# Sensor_Box_LoRa.net
KiCad netlist of a schematic drawn in Altium Designer
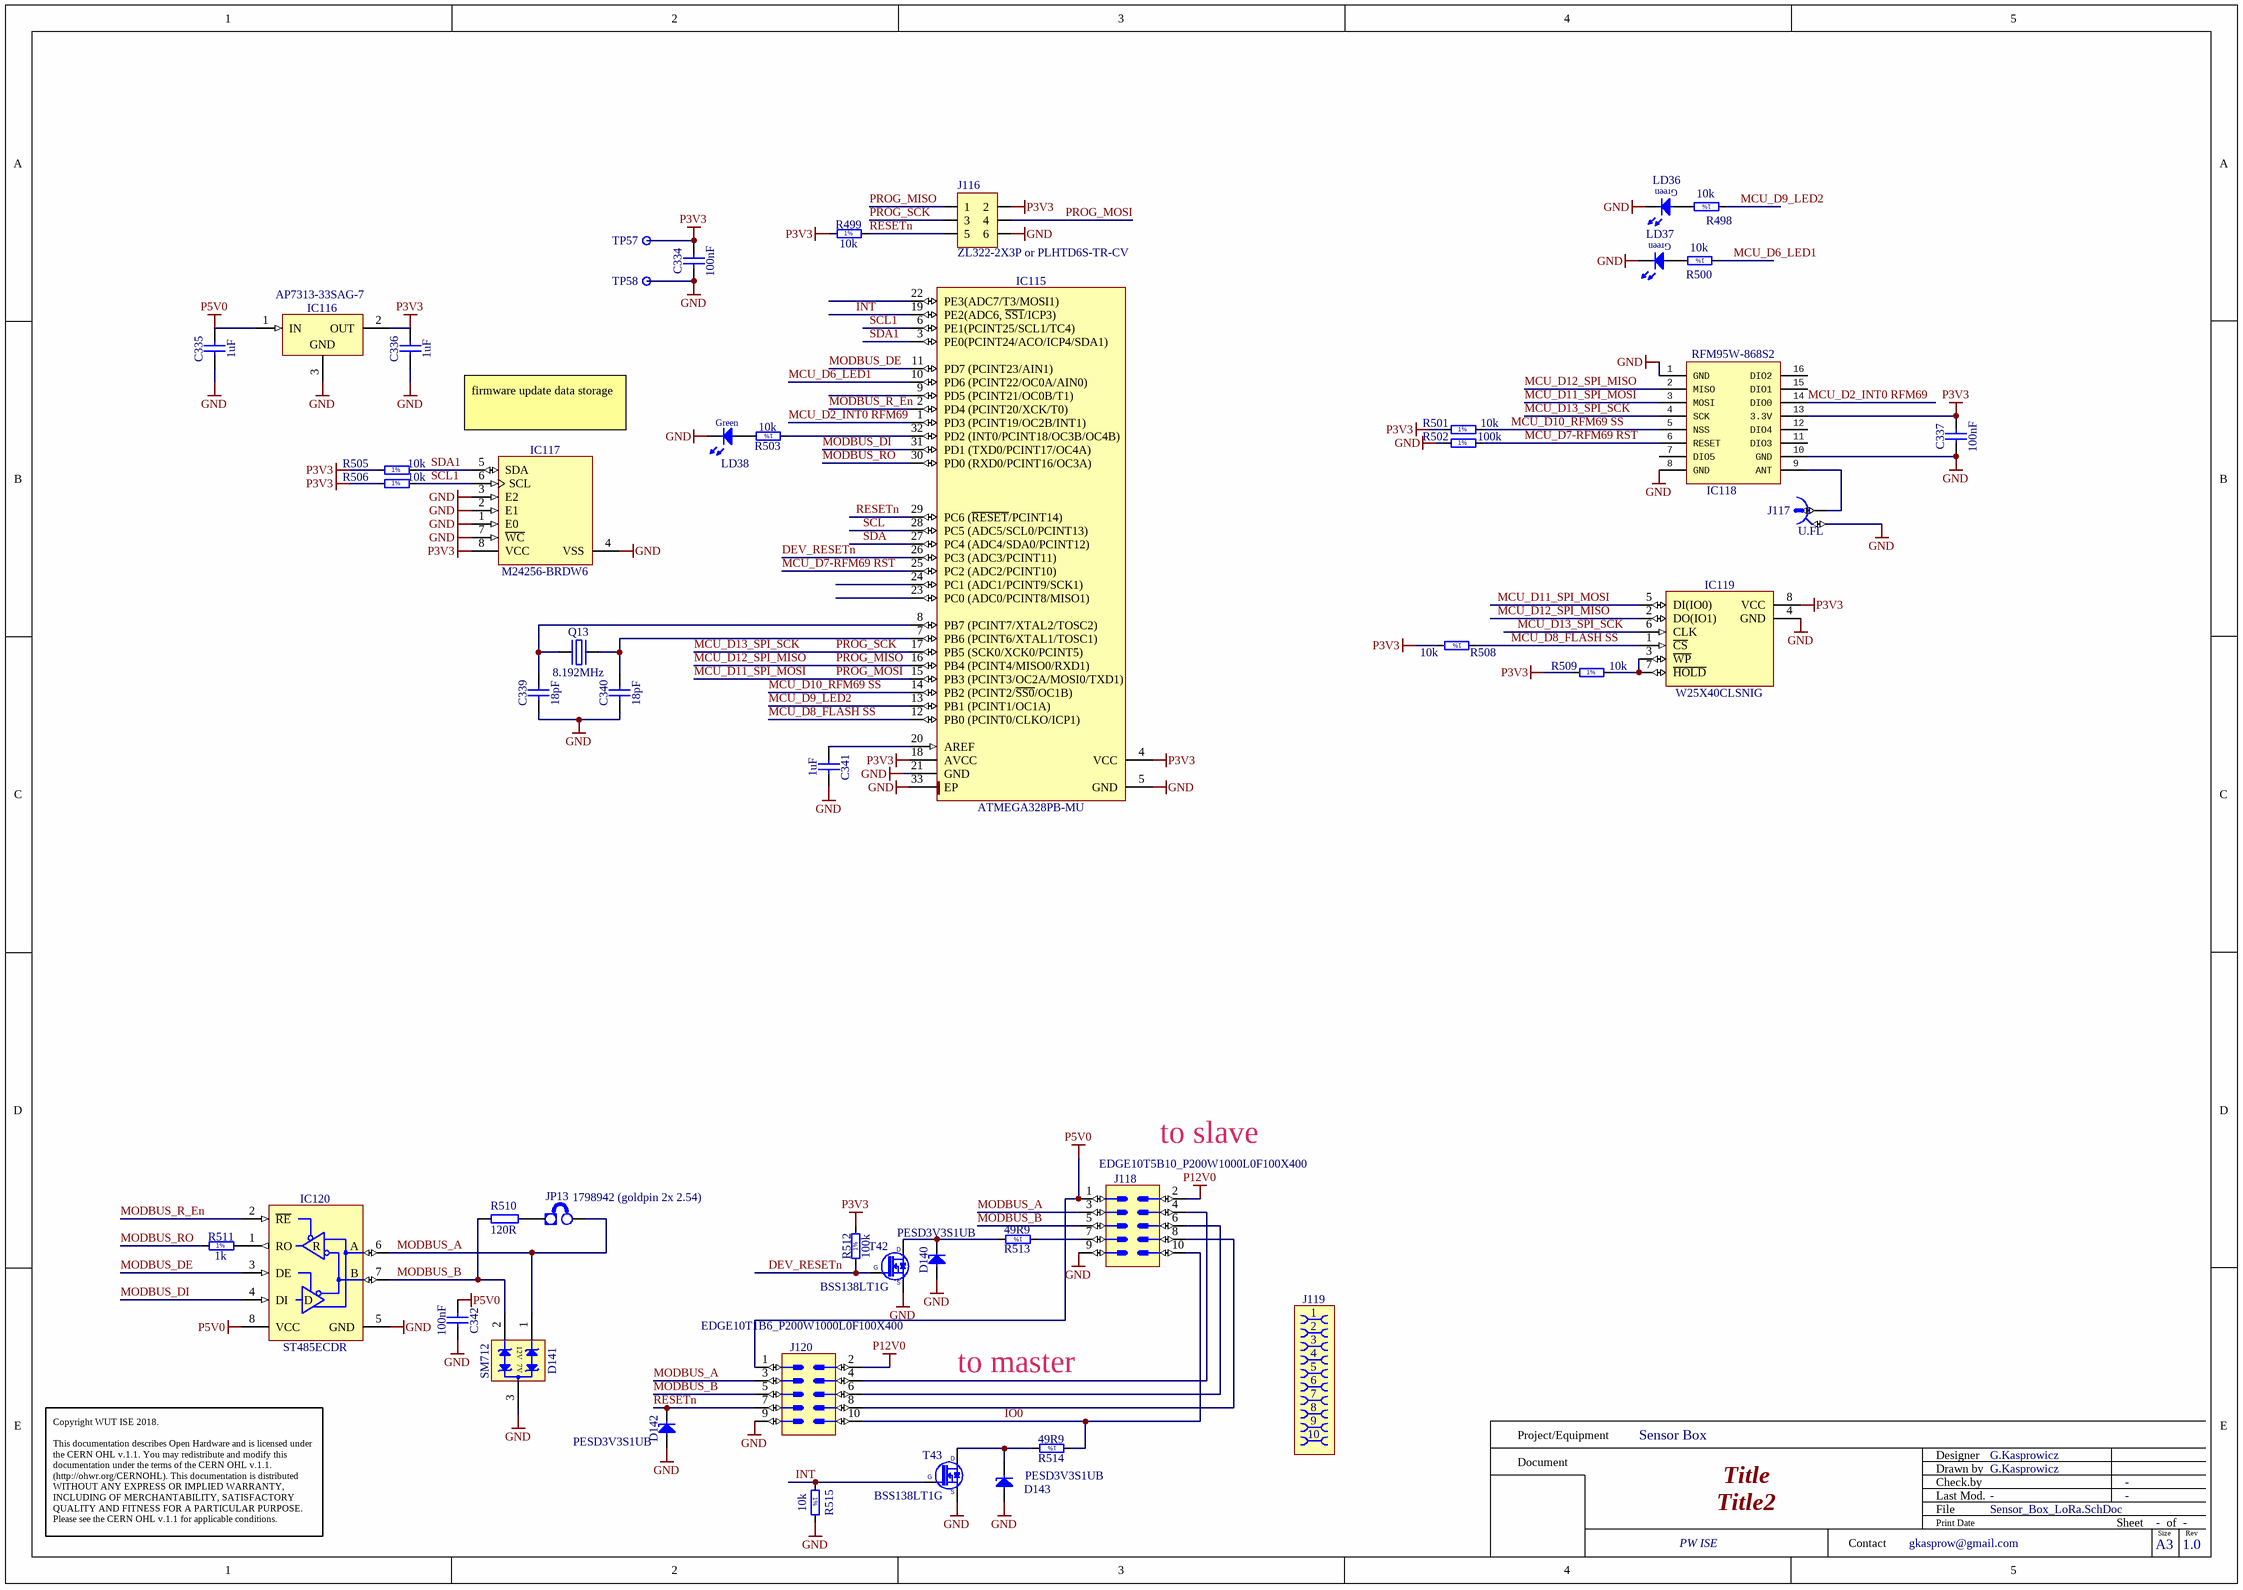
[diagram p0: Sensor_Box_LoRa.SchDoc]

(export (version "E")
  (design (tool "Eeschema 10.0.6"))
  (components
    (comp (ref "C334")
      (value "100nF")
      (footprint "CAPC1005X55N")
      (description "Non-polarised capacitor")
      (fields
        (field (name "PART NUMBER") "CC0402_100NF_16V_10%_X5R")
        (field (name "VOLTAGE") "16V")
        (field (name "AUTHOR") "CERN DEM JLC")
      )
      (libsource (lib "Capacitors") (part "Capacitor - non polarized"))
    )
    (comp (ref "C335")
      (value "1uF")
      (footprint "CAPC1005X55N")
      (description "Non-polarised capacitor")
      (fields
        (field (name "PART NUMBER") "CC0402_1UF_16V_10%_X5R")
        (field (name "VOLTAGE") "16V")
        (field (name "AUTHOR") "CERN DEM JLC")
      )
      (libsource (lib "Capacitors") (part "Capacitor - non polarized"))
    )
    (comp (ref "C336")
      (value "1uF")
      (footprint "CAPC1005X55N")
      (description "Non-polarised capacitor")
      (fields
        (field (name "PART NUMBER") "CC0402_1UF_16V_10%_X5R")
        (field (name "VOLTAGE") "16V")
        (field (name "AUTHOR") "CERN DEM JLC")
      )
      (libsource (lib "Capacitors") (part "Capacitor - non polarized"))
    )
    (comp (ref "C337")
      (value "100nF")
      (footprint "CAPC1005X55N")
      (description "Non-polarised capacitor")
      (fields
        (field (name "PART NUMBER") "CC0402_100NF_16V_10%_X5R")
        (field (name "VOLTAGE") "16V")
        (field (name "AUTHOR") "CERN DEM JLC")
      )
      (libsource (lib "Capacitors") (part "Capacitor - non polarized"))
    )
    (comp (ref "C339")
      (value "18pF")
      (footprint "CAPC1005X55N")
      (description "Non-polarised capacitor")
      (fields
        (field (name "PART NUMBER") "CC0402_18PF_50V_5%_C0G")
        (field (name "VOLTAGE") "50V")
        (field (name "AUTHOR") "CERN DEM JLC")
      )
      (libsource (lib "Capacitors") (part "Capacitor - non polarized"))
    )
    (comp (ref "C340")
      (value "18pF")
      (footprint "CAPC1005X55N")
      (description "Non-polarised capacitor")
      (fields
        (field (name "PART NUMBER") "CC0402_18PF_50V_5%_C0G")
        (field (name "VOLTAGE") "50V")
        (field (name "AUTHOR") "CERN DEM JLC")
      )
      (libsource (lib "Capacitors") (part "Capacitor - non polarized"))
    )
    (comp (ref "C341")
      (value "1uF")
      (footprint "CAPC1005X55N")
      (description "Non-polarised capacitor")
      (fields
        (field (name "PART NUMBER") "CC0402_1UF_16V_10%_X5R")
        (field (name "VOLTAGE") "16V")
        (field (name "AUTHOR") "CERN DEM JLC")
      )
      (libsource (lib "Capacitors") (part "Capacitor - non polarized"))
    )
    (comp (ref "C342")
      (value "100nF")
      (footprint "CAPC1005X55N")
      (description "Non-polarised capacitor")
      (fields
        (field (name "PART NUMBER") "CC0402_100NF_16V_10%_X7R")
        (field (name "VOLTAGE") "16V")
        (field (name "AUTHOR") "CERN DEM JLC")
      )
      (libsource (lib "Capacitors") (part "Capacitor - non polarized"))
    )
    (comp (ref "D140")
      (value "PESD3V3S1UB")
      (footprint "SODFL1608X65N")
      (description "ESD protection diode")
      (fields
        (field (name "VOLTAGE") "3V3")
        (field (name "POWER") "330W")
        (field (name "AUTHOR") "CERN DEM JLC")
      )
      (libsource (lib "ICs And Semiconductors") (part "Diode ESD"))
    )
    (comp (ref "D141")
      (value "SM712")
      (footprint "SOT95P237X112-3N")
      (description "Asymmetrical TVS Diode for Extended Common-Mode RS-485")
      (fields
        (field (name "VOLTAGE") "12V/-7V")
        (field (name "POWER") "400W")
        (field (name "AUTHOR") "CERN DEM JLC")
      )
      (libsource (lib "ICs And Semiconductors") (part "SM712"))
    )
    (comp (ref "D142")
      (value "PESD3V3S1UB")
      (footprint "SODFL1608X65N")
      (description "ESD protection diode")
      (fields
        (field (name "VOLTAGE") "3V3")
        (field (name "POWER") "330W")
        (field (name "AUTHOR") "CERN DEM JLC")
      )
      (libsource (lib "ICs And Semiconductors") (part "Diode ESD"))
    )
    (comp (ref "D143")
      (value "PESD3V3S1UB")
      (footprint "SODFL1608X65N")
      (description "ESD protection diode")
      (fields
        (field (name "VOLTAGE") "3V3")
        (field (name "POWER") "330W")
        (field (name "AUTHOR") "CERN DEM JLC")
      )
      (libsource (lib "ICs And Semiconductors") (part "Diode ESD"))
    )
    (comp (ref "IC115")
      (value "ATMEGA328PB-MU")
      (footprint "QFN50P500X500X100-33N-S325")
      (description "8-bit AVR 20MHz Microcontroller With 32K Bytes In-System  Programmable  Flash")
      (fields (field (name "MANUFACTURER") "ATMEL") (field (name "AUTHOR") "GK"))
      (libsource (lib "LIBRARY_SCH") (part "UPC_ATMEGA328PB-MU"))
    )
    (comp (ref "IC116")
      (value "AP7313-33SAG-7")
      (footprint "SOT95P240X130-3N")
      (description "3-Terminal Regulator 1=IN 2=OUT 3=GND")
      (fields (field (name "MANUFACTURER") "DIODES INCORPORATED") (field (name "AUTHOR") "CERN DEM JLC"))
      (libsource (lib "ICs And Semiconductors") (part "REG3 1IN-2OUT-3GND"))
    )
    (comp (ref "IC117")
      (value "M24256-BRDW6")
      (footprint "SOP65P640X120-8N")
      (description "256-Kbit Serial I²C Bus EEPROM")
      (fields
        (field (name "PART NUMBER") "M24256-BRDW6P")
        (field (name "MANUFACTURER") "ST MICROELECTRONICS")
        (field (name "AUTHOR") "CERN DEM MR")
      )
      (libsource (lib "LIBRARY_SCH") (part "MEM_M24256-BRDW6P"))
    )
    (comp (ref "IC118")
      (value "RFM95W-868S2")
      (footprint "RFM95W")
      (description "Low Power LoRa Transceiver Module")
      (fields (field (name "MANUFACTURER") "HOPE MICROELECTRONICS") (field (name "AUTHOR") "GK"))
      (libsource (lib "LIBRARY_SCH") (part "RF_RFM95W"))
    )
    (comp (ref "IC119")
      (value "W25X40CLSNIG")
      (footprint "SOIC127P600X135-8N")
      (description "4M-bit Serial Flash Memory with uniform 4KB sectors and Dual SPI and QPI")
      (fields (field (name "MANUFACTURER") "WINBOND") (field (name "AUTHOR") "GK"))
      (libsource (lib "LIBRARY_SCH") (part "MEM_W25X40CLSNIG"))
    )
    (comp (ref "IC120")
      (value "ST485ECDR")
      (footprint "SOIC127P600X175-8N")
      (description "±15kV ESD-Protected, Low Power  RS-485/RS-422 Transceiver")
      (fields (field (name "MANUFACTURER") "ST MICROELECTRONICS") (field (name "AUTHOR") "CERN DEM MR"))
      (libsource (lib "ICs And Semiconductors") (part "ST485EC"))
    )
    (comp (ref "J116")
      (value "ZL322-2X3P or PLHTD6S-TR-CV")
      (footprint "ZL322-2X3P")
      (description "1.27 mm dual row goldpin (Maritex)")
      (libsource (lib "LIBRARY_SCH") (part "CON_2x3 1.27 SMT Male"))
    )
    (comp (ref "J117")
      (value "U.FL")
      (footprint "HIROSE_U.FL-R-SMT-1(10)")
      (fields
        (field (name "PART NUMBER") "HIROSE_U.FL-R-SMT-1(10)")
        (field (name "MANUFACTURER") "HIROSE (HRS)")
        (field (name "MANUFACTURER PART NUMBER") "U.FL-R-SMT-1(10)")
        (field (name "AUTHOR") "CERN DEM JLC")
      )
      (libsource (lib "Connectors") (part "Coax_1Male_1Shield"))
    )
    (comp (ref "J118")
      (value "~")
      (footprint "EDGE10T5B10_P200W1000L0F100X400")
      (description "PCB Edge Connector 10 (2x5)")
      (fields
        (field (name "PART NUMBER") "EDGE10T5B10_P200W1000L0F100X400")
        (field (name "AUTHOR") "CERN DEM MR")
      )
      (libsource (lib "Connectors") (part "PCB Edge Connector 10 (2x5)"))
    )
    (comp (ref "J119")
      (value "~")
      (footprint "AVX_00 9159 010 061 916")
      (description "Open Ended Card Edge Connector, 9159 Series")
      (fields
        (field (name "PART NUMBER") "AVX_00 9159 010 061 916")
        (field (name "MANUFACTURER") "AVX")
        (field (name "AUTHOR") "CERN DEM MR")
      )
      (libsource (lib "Connectors") (part "AVX_00 9159 010 061 916"))
    )
    (comp (ref "J120")
      (value "~")
      (footprint "EDGE10T1B6_P200W1000L0F100X400")
      (description "PCB Edge Connector 10 (2x5)")
      (fields
        (field (name "PART NUMBER") "EDGE10T1B6_P200W1000L0F100X400")
        (field (name "AUTHOR") "CERN DEM MR")
      )
      (libsource (lib "Connectors") (part "PCB Edge Connector 10 (2x5)"))
    )
    (comp (ref "JP13")
      (value "1798942 (goldpin 2x 2.54)")
      (footprint "jump")
      (description "Jumper")
      (libsource (lib "LIBRARY_SCH") (part "JUMPER"))
    )
    (comp (ref "LD36")
      (value "Green")
      (footprint "LED_KINGBRIGHT_KPTR3216")
      (description "LED Green 1A 2C")
      (fields
        (field (name "PART NUMBER") "LED_KINGBRIGHT_KPTR-3216CGCK")
        (field (name "MANUFACTURER") "KINGBRIGHT")
        (field (name "AUTHOR") "CERN DEM MR")
      )
      (libsource (lib "ICs And Semiconductors") (part "LED_KINGBRIGHT_KPTR-3216CGCK"))
    )
    (comp (ref "LD37")
      (value "Green")
      (footprint "LED_KINGBRIGHT_KPTR3216")
      (description "LED Green 1A 2C")
      (fields
        (field (name "PART NUMBER") "LED_KINGBRIGHT_KPTR-3216CGCK")
        (field (name "MANUFACTURER") "KINGBRIGHT")
        (field (name "AUTHOR") "CERN DEM MR")
      )
      (libsource (lib "ICs And Semiconductors") (part "LED_KINGBRIGHT_KPTR-3216CGCK"))
    )
    (comp (ref "LD38")
      (value "Green")
      (footprint "LED_KINGBRIGHT_KPH-1608CGCK")
      (description "LED Green 1C 2A")
      (fields
        (field (name "PART NUMBER") "LED_KINGBRIGHT_KPH-1608CGCK")
        (field (name "MANUFACTURER") "KINGBRIGHT")
        (field (name "AUTHOR") "CERN DEM JLC")
      )
      (libsource (lib "ICs And Semiconductors") (part "LED Green 1C 2A"))
    )
    (comp (ref "Q13")
      (value "8.192MHz")
      (footprint "XTAL_ABRACON_ABLS")
      (description "Quartz Crystal")
      (fields
        (field (name "PART NUMBER") "XTAL_8.192MHZ_ABRACON_ABLS-8.192MHZ-B2-T")
        (field (name "MANUFACTURER") "ABRACON")
        (field (name "AUTHOR") "CERN DEM MR")
      )
      (libsource (lib "ICs And Semiconductors") (part "Quartz Crystal"))
    )
    (comp (ref "R498")
      (value "10k")
      (footprint "RESC1005X40N")
      (description "Resistor - 1%")
      (fields
        (field (name "PART NUMBER") "R0402_10K_1%_0.0625W_100PPM")
        (field (name "POWER") "0.0625W")
        (field (name "AUTHOR") "CERN DEM JLC")
      )
      (libsource (lib "Resistors") (part "Resistor - 1%"))
    )
    (comp (ref "R499")
      (value "10k")
      (footprint "RESC1005X40N")
      (description "Resistor - 1%")
      (fields
        (field (name "PART NUMBER") "R0402_10K_1%_0.0625W_100PPM")
        (field (name "POWER") "0.0625W")
        (field (name "AUTHOR") "CERN DEM JLC")
      )
      (libsource (lib "Resistors") (part "Resistor - 1%"))
    )
    (comp (ref "R500")
      (value "10k")
      (footprint "RESC1005X40N")
      (description "Resistor - 1%")
      (fields
        (field (name "PART NUMBER") "R0402_10K_1%_0.0625W_100PPM")
        (field (name "POWER") "0.0625W")
        (field (name "AUTHOR") "CERN DEM JLC")
      )
      (libsource (lib "Resistors") (part "Resistor - 1%"))
    )
    (comp (ref "R501")
      (value "10k")
      (footprint "RESC1005X40N")
      (description "Resistor - 1%")
      (fields
        (field (name "PART NUMBER") "R0402_10K_1%_0.0625W_100PPM")
        (field (name "POWER") "0.0625W")
        (field (name "AUTHOR") "CERN DEM JLC")
      )
      (libsource (lib "Resistors") (part "Resistor - 1%"))
    )
    (comp (ref "R502")
      (value "100k")
      (footprint "RESC1005X40N")
      (description "Resistor - 1%")
      (fields
        (field (name "PART NUMBER") "R0402_100K_1%_0.0625W_100PPM")
        (field (name "POWER") "0.0625W")
        (field (name "AUTHOR") "CERN DEM JLC")
      )
      (libsource (lib "Resistors") (part "Resistor - 1%"))
    )
    (comp (ref "R503")
      (value "10k")
      (footprint "RESC1005X40N")
      (description "Resistor - 1%")
      (fields
        (field (name "PART NUMBER") "R0402_10K_1%_0.0625W_100PPM")
        (field (name "POWER") "0.0625W")
        (field (name "AUTHOR") "CERN DEM JLC")
      )
      (libsource (lib "Resistors") (part "Resistor - 1%"))
    )
    (comp (ref "R505")
      (value "10k")
      (footprint "RESC1005X40N")
      (description "Resistor - 1%")
      (fields
        (field (name "PART NUMBER") "R0402_10K_1%_0.0625W_100PPM")
        (field (name "POWER") "0.0625W")
        (field (name "AUTHOR") "CERN DEM JLC")
      )
      (libsource (lib "Resistors") (part "Resistor - 1%"))
    )
    (comp (ref "R506")
      (value "10k")
      (footprint "RESC1005X40N")
      (description "Resistor - 1%")
      (fields
        (field (name "PART NUMBER") "R0402_10K_1%_0.0625W_100PPM")
        (field (name "POWER") "0.0625W")
        (field (name "AUTHOR") "CERN DEM JLC")
      )
      (libsource (lib "Resistors") (part "Resistor - 1%"))
    )
    (comp (ref "R508")
      (value "10k")
      (footprint "RESC1005X40N")
      (description "Resistor - 1%")
      (fields
        (field (name "PART NUMBER") "R0402_10K_1%_0.0625W_100PPM")
        (field (name "POWER") "0.0625W")
        (field (name "AUTHOR") "CERN DEM JLC")
      )
      (libsource (lib "Resistors") (part "Resistor - 1%"))
    )
    (comp (ref "R509")
      (value "10k")
      (footprint "RESC1005X40N")
      (description "Resistor - 1%")
      (fields
        (field (name "PART NUMBER") "R0402_10K_1%_0.0625W_100PPM")
        (field (name "POWER") "0.0625W")
        (field (name "AUTHOR") "CERN DEM JLC")
      )
      (libsource (lib "Resistors") (part "Resistor - 1%"))
    )
    (comp (ref "R510")
      (value "120R")
      (footprint "1206R")
      (description "SMD Resistor")
      (libsource (lib "LIBRARY_SCH") (part "RES_1206"))
    )
    (comp (ref "R511")
      (value "1k")
      (footprint "RESC1005X40N")
      (description "Resistor - 1%")
      (fields
        (field (name "PART NUMBER") "R0402_1K_1%_0.0625W_100PPM")
        (field (name "POWER") "0.0625W")
        (field (name "AUTHOR") "CERN DEM JLC")
      )
      (libsource (lib "Resistors") (part "Resistor - 1%"))
    )
    (comp (ref "R512")
      (value "100k")
      (footprint "RESC1005X40N")
      (description "Resistor - 1%")
      (fields
        (field (name "PART NUMBER") "R0402_100K_1%_0.0625W_100PPM")
        (field (name "POWER") "0.0625W")
        (field (name "AUTHOR") "CERN DEM JLC")
      )
      (libsource (lib "Resistors") (part "Resistor - 1%"))
    )
    (comp (ref "R513")
      (value "49R9")
      (footprint "RESC1005X40N")
      (description "Resistor - 1%")
      (fields
        (field (name "PART NUMBER") "R0402_49R9_1%_0.0625W_100PPM")
        (field (name "POWER") "0.0625W")
        (field (name "AUTHOR") "CERN DEM JLC")
      )
      (libsource (lib "Resistors") (part "Resistor - 1%"))
    )
    (comp (ref "R514")
      (value "49R9")
      (footprint "RESC1005X40N")
      (description "Resistor - 1%")
      (fields
        (field (name "PART NUMBER") "R0402_49R9_1%_0.0625W_100PPM")
        (field (name "POWER") "0.0625W")
        (field (name "AUTHOR") "CERN DEM JLC")
      )
      (libsource (lib "Resistors") (part "Resistor - 1%"))
    )
    (comp (ref "R515")
      (value "10k")
      (footprint "RESC1005X40N")
      (description "Resistor - 1%")
      (fields
        (field (name "PART NUMBER") "R0402_10K_1%_0.0625W_100PPM")
        (field (name "POWER") "0.0625W")
        (field (name "AUTHOR") "CERN DEM JLC")
      )
      (libsource (lib "Resistors") (part "Resistor - 1%"))
    )
    (comp (ref "T42")
      (value "BSS138LT1G")
      (footprint "SOT95P240X110-3N")
      (description "N-CHANNEL MOSFET WITH DIODE")
      (fields (field (name "MANUFACTURER") "ON SEMICONDUCTOR") (field (name "AUTHOR") "CERN DEM JLC"))
      (libsource (lib "ICs And Semiconductors") (part "N-MOSFET-D 1G 2S 3D"))
    )
    (comp (ref "T43")
      (value "BSS138LT1G")
      (footprint "SOT95P240X110-3N")
      (description "N-CHANNEL MOSFET WITH DIODE")
      (fields (field (name "MANUFACTURER") "ON SEMICONDUCTOR") (field (name "AUTHOR") "CERN DEM JLC"))
      (libsource (lib "ICs And Semiconductors") (part "N-MOSFET-D 1G 2S 3D"))
    )
    (comp (ref "TP57")
      (value "Test Point")
      (footprint "TPS127")
      (fields (field (name "PART NUMBER") "SMD_PAD_1.27X1.27MM") (field (name "AUTHOR") "CERN DEM JLC"))
      (libsource (lib "Eletro-mechanical") (part "Test Point"))
    )
    (comp (ref "TP58")
      (value "Test Point")
      (footprint "TPS127")
      (fields (field (name "PART NUMBER") "SMD_PAD_1.27X1.27MM") (field (name "AUTHOR") "CERN DEM JLC"))
      (libsource (lib "Eletro-mechanical") (part "Test Point"))
    )
  )
  (nets
    (net (code "1") (name "/DEV_RESETn") (class "Default")
      (node (ref "IC115") (pin "26") (pinfunction "PC3_(ADC3/PCINT11)_26") (pintype "bidirectional"))
      (node (ref "R512") (pin "1") (pinfunction "1_1") (pintype "passive"))
      (node (ref "T42") (pin "1") (pinfunction "G_1") (pintype "passive"))
    )
    (net (code "2") (name "/INT") (class "Default")
      (node (ref "IC115") (pin "19") (pinfunction "PE2(ADC6,_~{SS1}/ICP3)_19") (pintype "bidirectional"))
      (node (ref "R515") (pin "1") (pinfunction "1_1") (pintype "passive"))
      (node (ref "T43") (pin "1") (pinfunction "G_1") (pintype "passive"))
    )
    (net (code "3") (name "/IO0") (class "Default")
      (node (ref "J118") (pin "10") (pinfunction "10_10") (pintype "bidirectional"))
      (node (ref "J120") (pin "10") (pinfunction "10_10") (pintype "bidirectional"))
      (node (ref "R514") (pin "1") (pinfunction "1_1") (pintype "passive"))
    )
    (net (code "4") (name "/MCU_D2_INT0 RFM69") (class "Default")
      (node (ref "IC115") (pin "1") (pinfunction "PD3_(PCINT19/OC2B/INT1)_1") (pintype "bidirectional"))
      (node (ref "IC118") (pin "14") (pinfunction "DIO0_14") (pintype "passive"))
    )
    (net (code "5") (name "/MCU_D6_LED1") (class "Default")
      (node (ref "IC115") (pin "10") (pinfunction "PD6_(PCINT22/OC0A/AIN0)_10") (pintype "bidirectional"))
      (node (ref "R500") (pin "1") (pinfunction "1_1") (pintype "passive"))
    )
    (net (code "6") (name "/MCU_D7-RFM69 RST") (class "Default")
      (node (ref "IC115") (pin "25") (pinfunction "PC2_(ADC2/PCINT10)_25") (pintype "bidirectional"))
      (node (ref "IC118") (pin "6") (pinfunction "RESET_6") (pintype "passive"))
      (node (ref "R502") (pin "2") (pinfunction "2_2") (pintype "passive"))
    )
    (net (code "7") (name "/MCU_D8_FLASH SS") (class "Default")
      (node (ref "IC115") (pin "12") (pinfunction "PB0_(PCINT0/CLKO/ICP1)_12") (pintype "bidirectional"))
      (node (ref "IC119") (pin "1") (pinfunction "~{CS}_1") (pintype "input"))
      (node (ref "R508") (pin "1") (pinfunction "1_1") (pintype "passive"))
    )
    (net (code "8") (name "/MCU_D9_LED2") (class "Default")
      (node (ref "IC115") (pin "13") (pinfunction "PB1_(PCINT1/OC1A)_13") (pintype "bidirectional"))
      (node (ref "R498") (pin "1") (pinfunction "1_1") (pintype "passive"))
    )
    (net (code "9") (name "/MCU_D10_RFM69 SS") (class "Default")
      (node (ref "IC115") (pin "14") (pinfunction "PB2_(PCINT2/~{SS0}/OC1B)_14") (pintype "bidirectional"))
      (node (ref "IC118") (pin "5") (pinfunction "NSS_5") (pintype "passive"))
      (node (ref "R501") (pin "2") (pinfunction "2_2") (pintype "passive"))
    )
    (net (code "10") (name "/MCU_D11_SPI_MOSI") (class "Default")
      (node (ref "IC115") (pin "15") (pinfunction "PB3_(PCINT3/OC2A/MOSI0/TXD1)_15") (pintype "bidirectional"))
      (node (ref "IC118") (pin "3") (pinfunction "MOSI_3") (pintype "passive"))
      (node (ref "IC119") (pin "5") (pinfunction "DI(IO0)_5") (pintype "bidirectional"))
      (node (ref "J116") (pin "4") (pinfunction "4_4") (pintype "passive"))
    )
    (net (code "11") (name "/MCU_D12_SPI_MISO") (class "Default")
      (node (ref "IC115") (pin "16") (pinfunction "PB4_(PCINT4/MISO0/RXD1)_16") (pintype "bidirectional"))
      (node (ref "IC118") (pin "2") (pinfunction "MISO_2") (pintype "passive"))
      (node (ref "IC119") (pin "2") (pinfunction "DO(IO1)_2") (pintype "bidirectional"))
      (node (ref "J116") (pin "1") (pinfunction "1_1") (pintype "passive"))
    )
    (net (code "12") (name "/MCU_D13_SPI_SCK") (class "Default")
      (node (ref "IC115") (pin "17") (pinfunction "PB5_(SCK0/XCK0/PCINT5)_17") (pintype "bidirectional"))
      (node (ref "IC118") (pin "4") (pinfunction "SCK_4") (pintype "passive"))
      (node (ref "IC119") (pin "6") (pinfunction "CLK_6") (pintype "input"))
      (node (ref "J116") (pin "3") (pinfunction "3_3") (pintype "passive"))
    )
    (net (code "13") (name "/MODBUS_A") (class "Default")
      (node (ref "D141") (pin "1") (pinfunction "I/O1_1") (pintype "passive"))
      (node (ref "IC120") (pin "6") (pinfunction "A_6") (pintype "bidirectional"))
      (node (ref "J118") (pin "3") (pinfunction "3_3") (pintype "bidirectional"))
      (node (ref "J120") (pin "3") (pinfunction "3_3") (pintype "bidirectional"))
      (node (ref "JP13") (pin "2") (pinfunction "E2_2") (pintype "passive"))
    )
    (net (code "14") (name "/MODBUS_B") (class "Default")
      (node (ref "D141") (pin "2") (pinfunction "I/O2_2") (pintype "passive"))
      (node (ref "IC120") (pin "7") (pinfunction "B_7") (pintype "bidirectional"))
      (node (ref "J118") (pin "5") (pinfunction "5_5") (pintype "bidirectional"))
      (node (ref "J120") (pin "5") (pinfunction "5_5") (pintype "bidirectional"))
      (node (ref "R510") (pin "1") (pinfunction "1_1") (pintype "passive"))
    )
    (net (code "15") (name "/MODBUS_DE") (class "Default")
      (node (ref "IC115") (pin "11") (pinfunction "PD7_(PCINT23/AIN1)_11") (pintype "bidirectional"))
      (node (ref "IC120") (pin "3") (pinfunction "DE_3") (pintype "input"))
    )
    (net (code "16") (name "/MODBUS_DI") (class "Default")
      (node (ref "IC115") (pin "31") (pinfunction "PD1_(TXD0/PCINT17/OC4A)_31") (pintype "bidirectional"))
      (node (ref "IC120") (pin "4") (pinfunction "DI_4") (pintype "input"))
    )
    (net (code "17") (name "/MODBUS_RO") (class "Default")
      (node (ref "IC115") (pin "30") (pinfunction "PD0_(RXD0/PCINT16/OC3A)_30") (pintype "bidirectional"))
      (node (ref "R511") (pin "1") (pinfunction "1_1") (pintype "passive"))
    )
    (net (code "18") (name "/MODBUS_R_En") (class "Default")
      (node (ref "IC115") (pin "2") (pinfunction "PD4_(PCINT20/XCK/T0)_2") (pintype "bidirectional"))
      (node (ref "IC120") (pin "2") (pinfunction "~{RE}_2") (pintype "input"))
    )
    (net (code "19") (name "/RESETn") (class "Default")
      (node (ref "D142") (pin "1") (pinfunction "C_1") (pintype "passive"))
      (node (ref "IC115") (pin "29") (pinfunction "PC6_(~{RESET}/PCINT14)_29") (pintype "bidirectional"))
      (node (ref "J116") (pin "5") (pinfunction "5_5") (pintype "passive"))
      (node (ref "J120") (pin "7") (pinfunction "7_7") (pintype "bidirectional"))
      (node (ref "R499") (pin "2") (pinfunction "2_2") (pintype "passive"))
    )
    (net (code "20") (name "/SCL") (class "Default")
      (node (ref "IC115") (pin "28") (pinfunction "PC5_(ADC5/SCL0/PCINT13)_28") (pintype "bidirectional"))
    )
    (net (code "21") (name "/SCL1") (class "Default")
      (node (ref "IC115") (pin "6") (pinfunction "PE1(PCINT25/SCL1/TC4)_6") (pintype "bidirectional"))
      (node (ref "IC117") (pin "6") (pinfunction "SCL_6") (pintype "input"))
      (node (ref "R506") (pin "2") (pinfunction "2_2") (pintype "passive"))
    )
    (net (code "22") (name "/SDA") (class "Default")
      (node (ref "IC115") (pin "27") (pinfunction "PC4_(ADC4/SDA0/PCINT12)_27") (pintype "bidirectional"))
    )
    (net (code "23") (name "/SDA1") (class "Default")
      (node (ref "IC115") (pin "3") (pinfunction "PE0(PCINT24/ACO/ICP4/SDA1)_3") (pintype "bidirectional"))
      (node (ref "IC117") (pin "5") (pinfunction "SDA_5") (pintype "bidirectional"))
      (node (ref "R505") (pin "2") (pinfunction "2_2") (pintype "passive"))
    )
    (net (code "24") (name "GND") (class "Default")
      (node (ref "C334") (pin "1") (pinfunction "1_1") (pintype "passive"))
      (node (ref "C335") (pin "1") (pinfunction "1_1") (pintype "passive"))
      (node (ref "C336") (pin "1") (pinfunction "1_1") (pintype "passive"))
      (node (ref "C337") (pin "1") (pinfunction "1_1") (pintype "passive"))
      (node (ref "C339") (pin "1") (pinfunction "1_1") (pintype "passive"))
      (node (ref "C340") (pin "1") (pinfunction "1_1") (pintype "passive"))
      (node (ref "C341") (pin "2") (pinfunction "2_2") (pintype "passive"))
      (node (ref "C342") (pin "2") (pinfunction "2_2") (pintype "passive"))
      (node (ref "D140") (pin "2") (pinfunction "A_2") (pintype "passive"))
      (node (ref "D141") (pin "3") (pinfunction "GND_3") (pintype "passive"))
      (node (ref "D142") (pin "2") (pinfunction "A_2") (pintype "passive"))
      (node (ref "D143") (pin "2") (pinfunction "A_2") (pintype "passive"))
      (node (ref "IC115") (pin "21") (pinfunction "GND_21") (pintype "power_in"))
      (node (ref "IC115") (pin "33") (pinfunction "EP_33") (pintype "power_in"))
      (node (ref "IC115") (pin "5") (pinfunction "GND_5") (pintype "power_in"))
      (node (ref "IC116") (pin "3") (pinfunction "GND_3") (pintype "power_in"))
      (node (ref "IC117") (pin "1") (pinfunction "E0_1") (pintype "input"))
      (node (ref "IC117") (pin "2") (pinfunction "E1_2") (pintype "input"))
      (node (ref "IC117") (pin "3") (pinfunction "E2_3") (pintype "input"))
      (node (ref "IC117") (pin "4") (pinfunction "VSS_4") (pintype "power_in"))
      (node (ref "IC117") (pin "7") (pinfunction "~{WC}_7") (pintype "input"))
      (node (ref "IC118") (pin "1") (pinfunction "GND_1") (pintype "power_in"))
      (node (ref "IC118") (pin "10") (pinfunction "GND_10") (pintype "power_in"))
      (node (ref "IC118") (pin "8") (pinfunction "GND_8") (pintype "power_in"))
      (node (ref "IC119") (pin "4") (pinfunction "GND_4") (pintype "power_in"))
      (node (ref "IC120") (pin "5") (pinfunction "GND_5") (pintype "power_in"))
      (node (ref "J116") (pin "6") (pinfunction "6_6") (pintype "passive"))
      (node (ref "J117") (pin "2") (pinfunction "2_2") (pintype "bidirectional"))
      (node (ref "J118") (pin "9") (pinfunction "9_9") (pintype "bidirectional"))
      (node (ref "J120") (pin "9") (pinfunction "9_9") (pintype "bidirectional"))
      (node (ref "LD36") (pin "1") (pinfunction "C_1") (pintype "passive"))
      (node (ref "LD37") (pin "1") (pinfunction "C_1") (pintype "passive"))
      (node (ref "LD38") (pin "1") (pinfunction "C_1") (pintype "passive"))
      (node (ref "R502") (pin "1") (pinfunction "1_1") (pintype "passive"))
      (node (ref "R515") (pin "2") (pinfunction "2_2") (pintype "passive"))
      (node (ref "T42") (pin "2") (pinfunction "S_2") (pintype "passive"))
      (node (ref "T43") (pin "2") (pinfunction "S_2") (pintype "passive"))
      (node (ref "TP58") (pin "1") (pinfunction "1_1") (pintype "bidirectional"))
    )
    (net (code "25") (name "Net-(D140-C)") (class "Default")
      (node (ref "D140") (pin "1") (pinfunction "C_1") (pintype "passive"))
      (node (ref "R513") (pin "2") (pinfunction "2_2") (pintype "passive"))
      (node (ref "T42") (pin "3") (pinfunction "D_3") (pintype "passive"))
    )
    (net (code "26") (name "Net-(D143-C)") (class "Default")
      (node (ref "D143") (pin "1") (pinfunction "C_1") (pintype "passive"))
      (node (ref "R514") (pin "2") (pinfunction "2_2") (pintype "passive"))
      (node (ref "T43") (pin "3") (pinfunction "D_3") (pintype "passive"))
    )
    (net (code "27") (name "Net-(IC115-AREF)") (class "Default")
      (node (ref "C341") (pin "1") (pinfunction "1_1") (pintype "passive"))
      (node (ref "IC115") (pin "20") (pinfunction "AREF_20") (pintype "input"))
    )
    (net (code "28") (name "Net-(IC115-PB6_(PCINT6{slash}XTAL1{slash}TOSC1))") (class "Default")
      (node (ref "C340") (pin "2") (pinfunction "2_2") (pintype "passive"))
      (node (ref "IC115") (pin "7") (pinfunction "PB6_(PCINT6/XTAL1/TOSC1)_7") (pintype "bidirectional"))
      (node (ref "Q13") (pin "2") (pinfunction "OSC2_2") (pintype "passive"))
    )
    (net (code "29") (name "Net-(IC115-PB7_(PCINT7{slash}XTAL2{slash}TOSC2))") (class "Default")
      (node (ref "C339") (pin "2") (pinfunction "2_2") (pintype "passive"))
      (node (ref "IC115") (pin "8") (pinfunction "PB7_(PCINT7/XTAL2/TOSC2)_8") (pintype "bidirectional"))
      (node (ref "Q13") (pin "1") (pinfunction "OSC1_1") (pintype "passive"))
    )
    (net (code "30") (name "Net-(IC115-PD2_(INT0{slash}PCINT18{slash}OC3B{slash}OC4B))") (class "Default")
      (node (ref "IC115") (pin "32") (pinfunction "PD2_(INT0/PCINT18/OC3B/OC4B)_32") (pintype "bidirectional"))
      (node (ref "R503") (pin "1") (pinfunction "1_1") (pintype "passive"))
    )
    (net (code "31") (name "Net-(IC118-ANT)") (class "Default")
      (node (ref "IC118") (pin "9") (pinfunction "ANT_9") (pintype "passive"))
      (node (ref "J117") (pin "1") (pinfunction "1_1") (pintype "bidirectional"))
    )
    (net (code "32") (name "Net-(IC119-~{HOLD})") (class "Default")
      (node (ref "IC119") (pin "3") (pinfunction "~{WP}_3") (pintype "bidirectional"))
      (node (ref "IC119") (pin "7") (pinfunction "~{HOLD}_7") (pintype "bidirectional"))
      (node (ref "R509") (pin "2") (pinfunction "2_2") (pintype "passive"))
    )
    (net (code "33") (name "Net-(IC120-RO)") (class "Default")
      (node (ref "IC120") (pin "1") (pinfunction "RO_1") (pintype "output"))
      (node (ref "R511") (pin "2") (pinfunction "2_2") (pintype "passive"))
    )
    (net (code "34") (name "Net-(J118-Pad4)") (class "Default")
      (node (ref "J118") (pin "4") (pinfunction "4_4") (pintype "bidirectional"))
      (node (ref "J120") (pin "4") (pinfunction "4_4") (pintype "bidirectional"))
    )
    (net (code "35") (name "Net-(J118-Pad6)") (class "Default")
      (node (ref "J118") (pin "6") (pinfunction "6_6") (pintype "bidirectional"))
      (node (ref "J120") (pin "6") (pinfunction "6_6") (pintype "bidirectional"))
    )
    (net (code "36") (name "Net-(J118-Pad7)") (class "Default")
      (node (ref "J118") (pin "7") (pinfunction "7_7") (pintype "bidirectional"))
      (node (ref "R513") (pin "1") (pinfunction "1_1") (pintype "passive"))
    )
    (net (code "37") (name "Net-(J118-Pad8)") (class "Default")
      (node (ref "J118") (pin "8") (pinfunction "8_8") (pintype "bidirectional"))
      (node (ref "J120") (pin "8") (pinfunction "8_8") (pintype "bidirectional"))
    )
    (net (code "38") (name "Net-(JP13-E1)") (class "Default")
      (node (ref "JP13") (pin "1") (pinfunction "E1_1") (pintype "passive"))
      (node (ref "R510") (pin "2") (pinfunction "2_2") (pintype "passive"))
    )
    (net (code "39") (name "Net-(LD36-A)") (class "Default")
      (node (ref "LD36") (pin "2") (pinfunction "A_2") (pintype "passive"))
      (node (ref "R498") (pin "2") (pinfunction "2_2") (pintype "passive"))
    )
    (net (code "40") (name "Net-(LD37-A)") (class "Default")
      (node (ref "LD37") (pin "2") (pinfunction "A_2") (pintype "passive"))
      (node (ref "R500") (pin "2") (pinfunction "2_2") (pintype "passive"))
    )
    (net (code "41") (name "Net-(LD38-A)") (class "Default")
      (node (ref "LD38") (pin "2") (pinfunction "A_2") (pintype "passive"))
      (node (ref "R503") (pin "2") (pinfunction "2_2") (pintype "passive"))
    )
    (net (code "42") (name "P3V3") (class "Default")
      (node (ref "C334") (pin "2") (pinfunction "2_2") (pintype "passive"))
      (node (ref "C336") (pin "2") (pinfunction "2_2") (pintype "passive"))
      (node (ref "C337") (pin "2") (pinfunction "2_2") (pintype "passive"))
      (node (ref "IC115") (pin "18") (pinfunction "AVCC_18") (pintype "power_in"))
      (node (ref "IC115") (pin "4") (pinfunction "VCC_4") (pintype "power_in"))
      (node (ref "IC116") (pin "2") (pinfunction "OUT_2") (pintype "power_in"))
      (node (ref "IC117") (pin "8") (pinfunction "VCC_8") (pintype "power_in"))
      (node (ref "IC118") (pin "13") (pinfunction "3.3V_13") (pintype "power_in"))
      (node (ref "IC119") (pin "8") (pinfunction "VCC_8") (pintype "power_in"))
      (node (ref "J116") (pin "2") (pinfunction "2_2") (pintype "passive"))
      (node (ref "R499") (pin "1") (pinfunction "1_1") (pintype "passive"))
      (node (ref "R501") (pin "1") (pinfunction "1_1") (pintype "passive"))
      (node (ref "R505") (pin "1") (pinfunction "1_1") (pintype "passive"))
      (node (ref "R506") (pin "1") (pinfunction "1_1") (pintype "passive"))
      (node (ref "R508") (pin "2") (pinfunction "2_2") (pintype "passive"))
      (node (ref "R509") (pin "1") (pinfunction "1_1") (pintype "passive"))
      (node (ref "R512") (pin "2") (pinfunction "2_2") (pintype "passive"))
      (node (ref "TP57") (pin "1") (pinfunction "1_1") (pintype "bidirectional"))
    )
    (net (code "43") (name "P5V0") (class "Default")
      (node (ref "C335") (pin "2") (pinfunction "2_2") (pintype "passive"))
      (node (ref "C342") (pin "1") (pinfunction "1_1") (pintype "passive"))
      (node (ref "IC116") (pin "1") (pinfunction "IN_1") (pintype "input"))
      (node (ref "IC120") (pin "8") (pinfunction "VCC_8") (pintype "power_in"))
      (node (ref "J118") (pin "1") (pinfunction "1_1") (pintype "bidirectional"))
      (node (ref "J120") (pin "1") (pinfunction "1_1") (pintype "bidirectional"))
    )
    (net (code "44") (name "P12V0") (class "Default")
      (node (ref "J118") (pin "2") (pinfunction "2_2") (pintype "bidirectional"))
      (node (ref "J120") (pin "2") (pinfunction "2_2") (pintype "bidirectional"))
    )
    (net (code "45") (name "unconnected-(IC115-PC0_(ADC0{slash}PCINT8{slash}MISO1)-Pad23)") (class "Default")
      (node (ref "IC115") (pin "23") (pinfunction "PC0_(ADC0/PCINT8/MISO1)_23") (pintype "bidirectional"))
    )
    (net (code "46") (name "unconnected-(IC115-PC1_(ADC1{slash}PCINT9{slash}SCK1)-Pad24)") (class "Default")
      (node (ref "IC115") (pin "24") (pinfunction "PC1_(ADC1/PCINT9/SCK1)_24") (pintype "bidirectional"))
    )
    (net (code "47") (name "unconnected-(IC115-PD5_(PCINT21{slash}OC0B{slash}T1)-Pad9)") (class "Default")
      (node (ref "IC115") (pin "9") (pinfunction "PD5_(PCINT21/OC0B/T1)_9") (pintype "bidirectional"))
    )
    (net (code "48") (name "unconnected-(IC115-PE3(ADC7{slash}T3{slash}MOSI1)-Pad22)") (class "Default")
      (node (ref "IC115") (pin "22") (pinfunction "PE3(ADC7/T3/MOSI1)_22") (pintype "bidirectional"))
    )
    (net (code "49") (name "unconnected-(IC118-DIO1-Pad15)") (class "Default")
      (node (ref "IC118") (pin "15") (pinfunction "DIO1_15") (pintype "passive"))
    )
    (net (code "50") (name "unconnected-(IC118-DIO2-Pad16)") (class "Default")
      (node (ref "IC118") (pin "16") (pinfunction "DIO2_16") (pintype "passive"))
    )
    (net (code "51") (name "unconnected-(IC118-DIO3-Pad11)") (class "Default")
      (node (ref "IC118") (pin "11") (pinfunction "DIO3_11") (pintype "passive"))
    )
    (net (code "52") (name "unconnected-(IC118-DIO4-Pad12)") (class "Default")
      (node (ref "IC118") (pin "12") (pinfunction "DIO4_12") (pintype "passive"))
    )
    (net (code "53") (name "unconnected-(IC118-DIO5-Pad7)") (class "Default")
      (node (ref "IC118") (pin "7") (pinfunction "DIO5_7") (pintype "passive"))
    )
  )
)
